# powerstrip2.net
KiCad netlist of a schematic drawn in Altium Designer
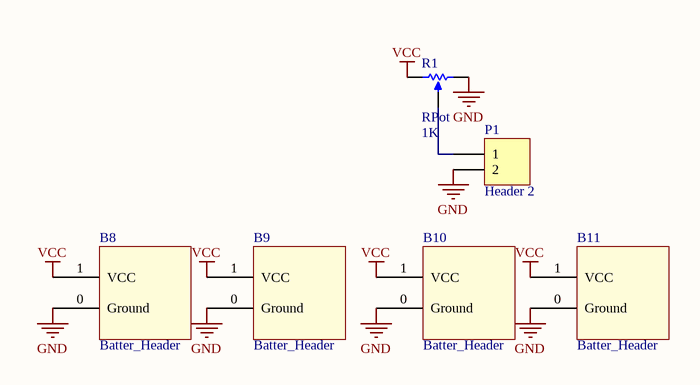
[diagram p0: powerstrip2.SchDoc]

(export (version "E")
  (design (tool "Eeschema 10.0.6"))
  (components
    (comp (ref "B8")
      (value "Batter_Header")
      (footprint "Battery_Header")
      (libsource (lib "battery header") (part "Batter_Header"))
    )
    (comp (ref "B9")
      (value "Batter_Header")
      (footprint "Battery_Header")
      (libsource (lib "battery header") (part "Batter_Header"))
    )
    (comp (ref "B10")
      (value "Batter_Header")
      (footprint "Battery_Header")
      (libsource (lib "battery header") (part "Batter_Header"))
    )
    (comp (ref "B11")
      (value "Batter_Header")
      (footprint "Battery_Header")
      (libsource (lib "battery header") (part "Batter_Header"))
    )
    (comp (ref "P1")
      (value "Header 2")
      (footprint "HDR1X2")
      (description "Header, 2-Pin")
      (fields (field (name "PUBLISHER") "Altium Limited"))
      (libsource (lib "Miscellaneous Connectors") (part "Header 2"))
    )
    (comp (ref "R1")
      (value "RPot")
      (footprint "VR5")
      (description "Potentiometer")
      (fields (field (name "ALTIUM_VALUE") "1K") (field (name "PUBLISHER") "Altium Limited"))
      (libsource (lib "Miscellaneous Devices") (part "RPot"))
    )
  )
  (nets
    (net (code "1") (name "GND") (class "Default")
      (node (ref "B10") (pin "0") (pinfunction "Ground_0") (pintype "passive"))
      (node (ref "B11") (pin "0") (pinfunction "Ground_0") (pintype "passive"))
      (node (ref "B8") (pin "0") (pinfunction "Ground_0") (pintype "passive"))
      (node (ref "B9") (pin "0") (pinfunction "Ground_0") (pintype "passive"))
      (node (ref "P1") (pin "2") (pinfunction "2_2") (pintype "passive"))
      (node (ref "R1") (pin "2") (pinfunction "BOT_2") (pintype "passive"))
    )
    (net (code "2") (name "Net-(R1-TAP)") (class "Default")
      (node (ref "P1") (pin "1") (pinfunction "1_1") (pintype "passive"))
      (node (ref "R1") (pin "3") (pinfunction "TAP_3") (pintype "passive"))
    )
    (net (code "3") (name "VCC") (class "Default")
      (node (ref "B10") (pin "1") (pinfunction "VCC_1") (pintype "passive"))
      (node (ref "B11") (pin "1") (pinfunction "VCC_1") (pintype "passive"))
      (node (ref "B8") (pin "1") (pinfunction "VCC_1") (pintype "passive"))
      (node (ref "B9") (pin "1") (pinfunction "VCC_1") (pintype "passive"))
      (node (ref "R1") (pin "1") (pinfunction "TOP_1") (pintype "passive"))
    )
  )
)
